# Page_04-LAN9254-Part1.net
KiCad netlist of a schematic drawn in Altium Designer
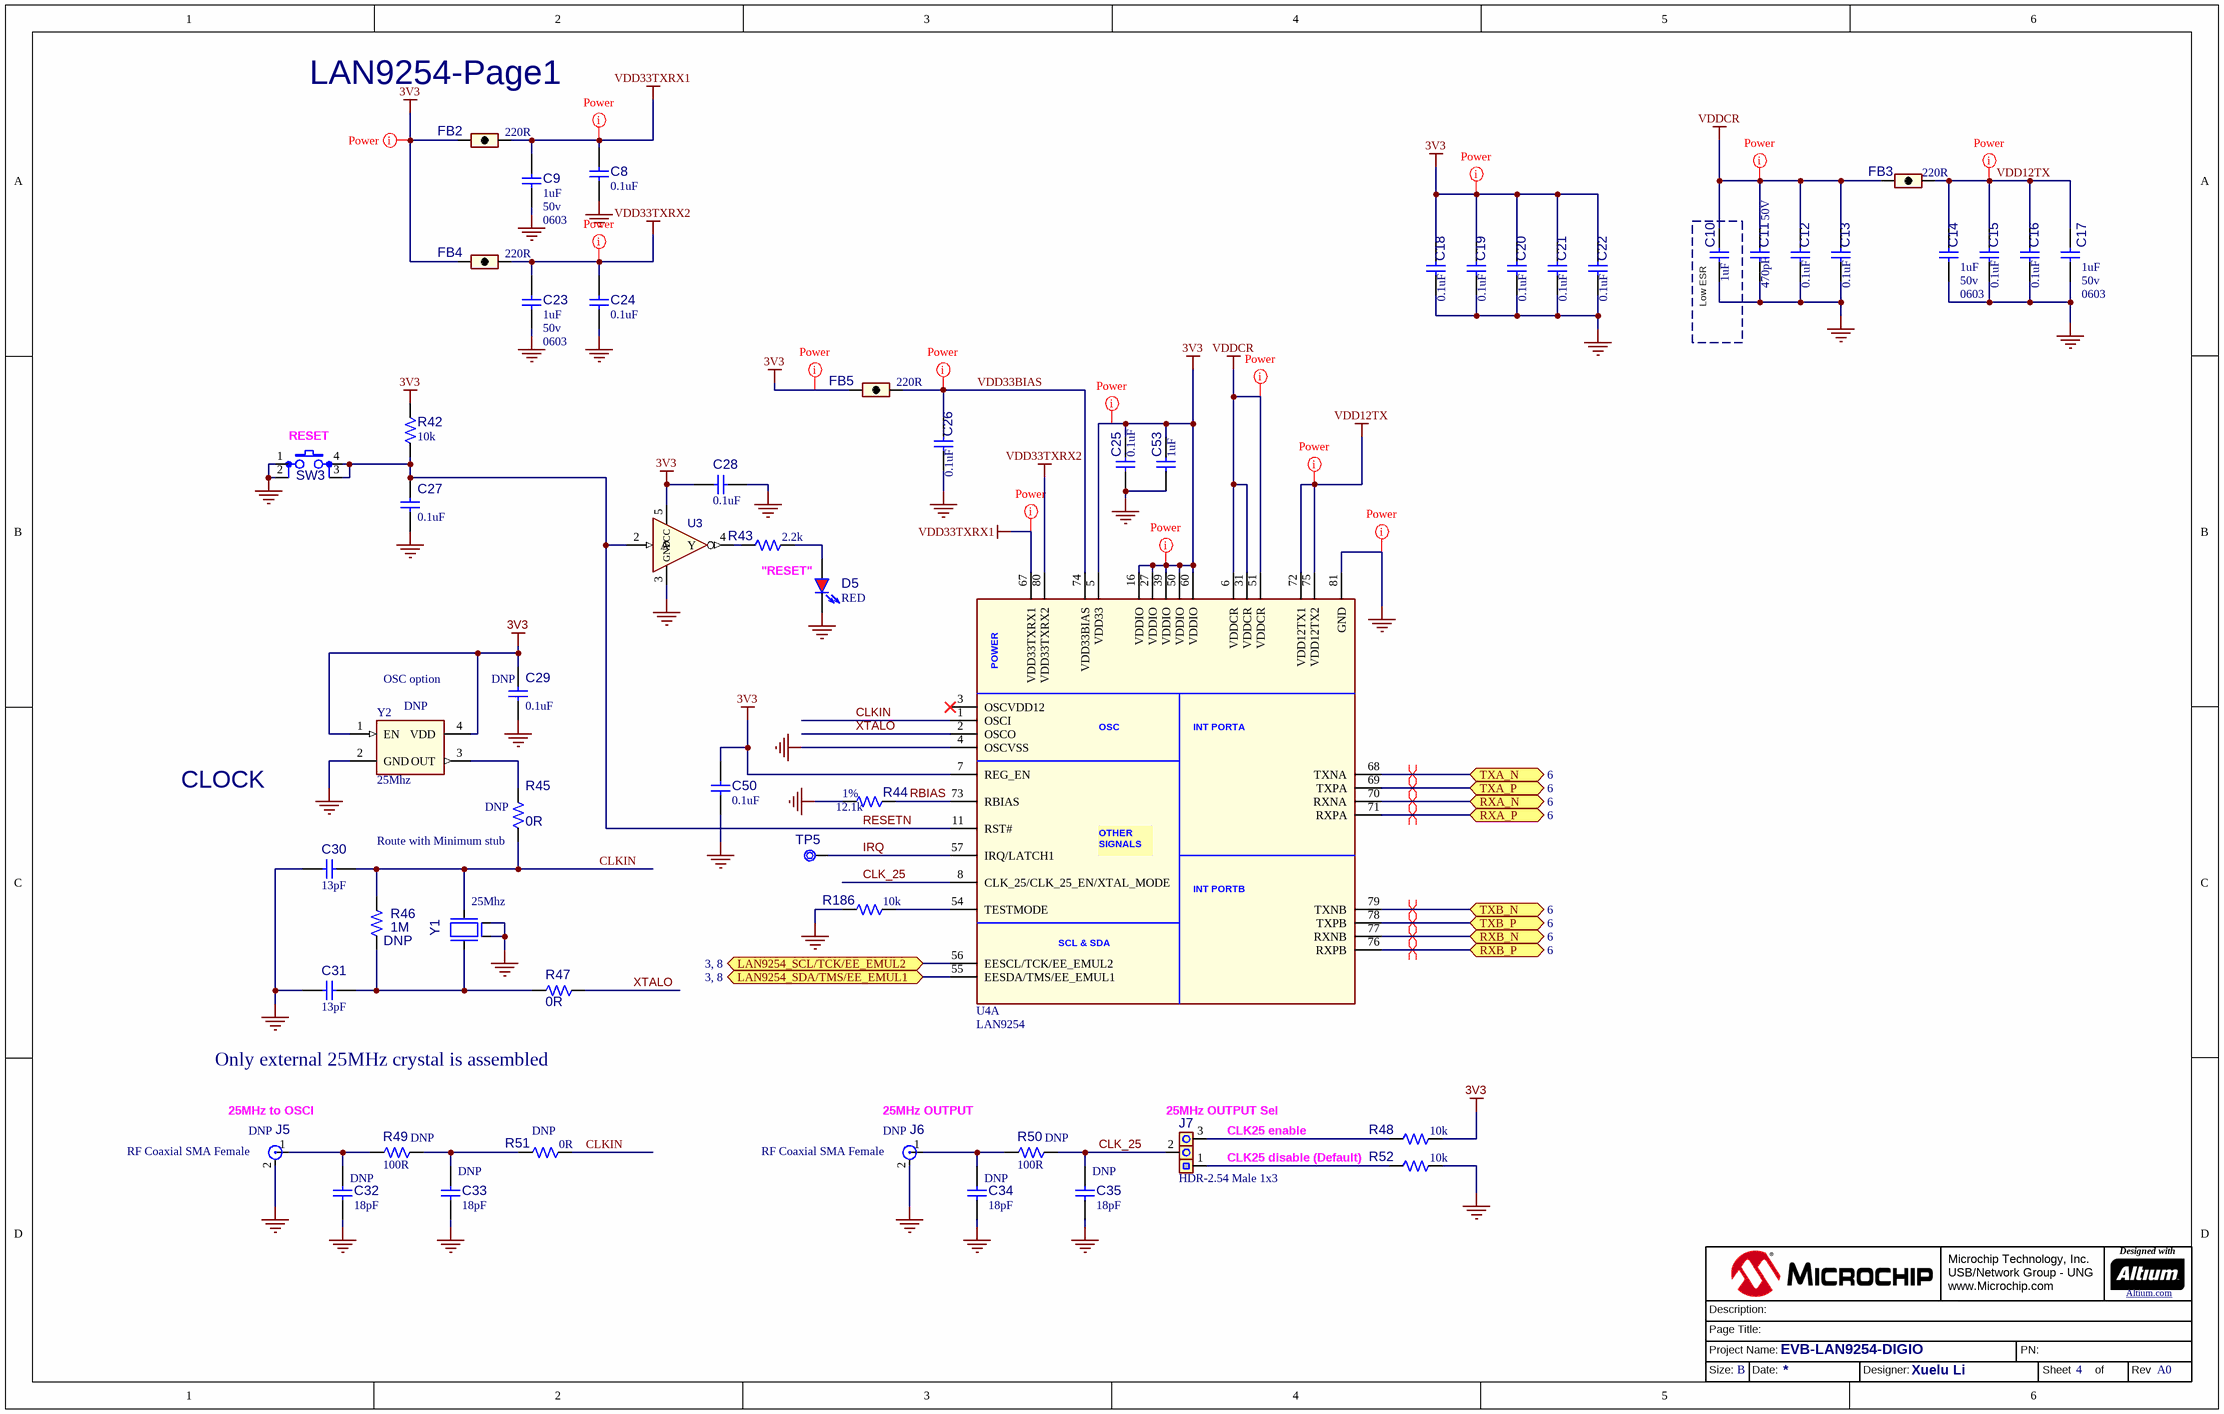
[diagram p0: Page 04-LAN9254-Part1.SchDoc]

(export (version "E")
  (design (tool "Eeschema 10.0.6"))
  (components
    (comp (ref "C8")
      (value "0.1uF")
      (footprint "CAP_C_0402")
      (description "Capacitor")
      (fields
        (field (name "VOLTAGE") "16V")
        (field (name "TOLERANCE") "10%")
        (field (name "OWNER") "Sompoch Loboonlert")
      )
      (libsource (lib "MCHP-CDB-Offline") (part "Capacitor NP"))
    )
    (comp (ref "C9")
      (value "1uF")
      (footprint "CAP_C_0603")
      (description "Capacitor")
      (fields
        (field (name "VOLTAGE") "50v")
        (field (name "PACKAGE") "0603")
        (field (name "TOLERANCE") "10%")
        (field (name "Comment") "Capacitor NP")
        (field (name "OWNER") "Sam Charles")
      )
      (libsource (lib "MCHP-CDB") (part "Capacitor NP"))
    )
    (comp (ref "C10")
      (value "1uF")
      (footprint "CAP_C_0603")
      (description "Capacitor")
      (fields (field (name "VOLTAGE") "50V") (field (name "TOLERANCE") "10%"))
      (libsource (lib "") (part "Capacitor NP_1"))
    )
    (comp (ref "C11")
      (value "470pF")
      (footprint "CAP_C_0402")
      (description "Capacitor")
      (fields
        (field (name "VOLTAGE") "50V")
        (field (name "TOLERANCE") "5%")
        (field (name "Comment") "Capacitor NP")
        (field (name "OWNER") "Duane Burt")
      )
      (libsource (lib "MCHP-CDB") (part "Capacitor NP"))
    )
    (comp (ref "C12")
      (value "0.1uF")
      (footprint "CAP_C_0402")
      (description "Capacitor")
      (fields
        (field (name "TOLERANCE") "10%")
        (field (name "Comment") "Capacitor NP")
        (field (name "OWNER") "Jamus Griego")
      )
      (libsource (lib "MCHP-CDB") (part "Capacitor NP"))
    )
    (comp (ref "C13")
      (value "0.1uF")
      (footprint "CAP_C_0402")
      (description "Capacitor")
      (fields
        (field (name "TOLERANCE") "10%")
        (field (name "Comment") "Capacitor NP")
        (field (name "OWNER") "Jamus Griego")
      )
      (libsource (lib "MCHP-CDB") (part "Capacitor NP"))
    )
    (comp (ref "C14")
      (value "1uF")
      (footprint "CAP_C_0603")
      (description "Capacitor")
      (fields
        (field (name "VOLTAGE") "50v")
        (field (name "PACKAGE") "0603")
        (field (name "TOLERANCE") "10%")
        (field (name "Comment") "Capacitor NP")
        (field (name "OWNER") "Sam Charles")
      )
      (libsource (lib "MCHP-CDB") (part "Capacitor NP"))
    )
    (comp (ref "C15")
      (value "0.1uF")
      (footprint "CAP_C_0402")
      (description "Capacitor")
      (fields
        (field (name "TOLERANCE") "10%")
        (field (name "Comment") "Capacitor NP")
        (field (name "OWNER") "Jamus Griego")
      )
      (libsource (lib "MCHP-CDB") (part "Capacitor NP"))
    )
    (comp (ref "C16")
      (value "0.1uF")
      (footprint "CAP_C_0402")
      (description "Capacitor")
      (fields
        (field (name "TOLERANCE") "10%")
        (field (name "Comment") "Capacitor NP")
        (field (name "OWNER") "Jamus Griego")
      )
      (libsource (lib "MCHP-CDB") (part "Capacitor NP"))
    )
    (comp (ref "C17")
      (value "1uF")
      (footprint "CAP_C_0603")
      (description "Capacitor")
      (fields
        (field (name "VOLTAGE") "50v")
        (field (name "PACKAGE") "0603")
        (field (name "TOLERANCE") "10%")
        (field (name "Comment") "Capacitor NP")
        (field (name "OWNER") "Sam Charles")
      )
      (libsource (lib "MCHP-CDB") (part "Capacitor NP"))
    )
    (comp (ref "C18")
      (value "0.1uF")
      (footprint "CAP_C_0402")
      (description "Capacitor")
      (fields
        (field (name "TOLERANCE") "10%")
        (field (name "Comment") "Capacitor NP")
        (field (name "OWNER") "Jamus Griego")
      )
      (libsource (lib "MCHP-CDB") (part "Capacitor NP"))
    )
    (comp (ref "C19")
      (value "0.1uF")
      (footprint "CAP_C_0402")
      (description "Capacitor")
      (fields
        (field (name "TOLERANCE") "10%")
        (field (name "Comment") "Capacitor NP")
        (field (name "OWNER") "Jamus Griego")
      )
      (libsource (lib "MCHP-CDB") (part "Capacitor NP"))
    )
    (comp (ref "C20")
      (value "0.1uF")
      (footprint "CAP_C_0402")
      (description "Capacitor")
      (fields
        (field (name "TOLERANCE") "10%")
        (field (name "Comment") "Capacitor NP")
        (field (name "OWNER") "Jamus Griego")
      )
      (libsource (lib "MCHP-CDB") (part "Capacitor NP"))
    )
    (comp (ref "C21")
      (value "0.1uF")
      (footprint "CAP_C_0402")
      (description "Capacitor")
      (fields
        (field (name "TOLERANCE") "10%")
        (field (name "Comment") "Capacitor NP")
        (field (name "OWNER") "Jamus Griego")
      )
      (libsource (lib "MCHP-CDB") (part "Capacitor NP"))
    )
    (comp (ref "C22")
      (value "0.1uF")
      (footprint "CAP_C_0402")
      (description "Capacitor")
      (fields
        (field (name "TOLERANCE") "10%")
        (field (name "Comment") "Capacitor NP")
        (field (name "OWNER") "Jamus Griego")
      )
      (libsource (lib "MCHP-CDB") (part "Capacitor NP"))
    )
    (comp (ref "C23")
      (value "1uF")
      (footprint "CAP_C_0603")
      (description "Capacitor")
      (fields
        (field (name "VOLTAGE") "50v")
        (field (name "PACKAGE") "0603")
        (field (name "TOLERANCE") "10%")
        (field (name "Comment") "Capacitor NP")
        (field (name "OWNER") "Sam Charles")
      )
      (libsource (lib "MCHP-CDB") (part "Capacitor NP"))
    )
    (comp (ref "C24")
      (value "0.1uF")
      (footprint "CAP_C_0402")
      (description "Capacitor")
      (fields
        (field (name "VOLTAGE") "16V")
        (field (name "TOLERANCE") "10%")
        (field (name "OWNER") "Sompoch Loboonlert")
      )
      (libsource (lib "MCHP-CDB-Offline") (part "Capacitor NP"))
    )
    (comp (ref "C25")
      (value "0.1uF")
      (footprint "CAP_C_0402")
      (description "Capacitor")
      (fields
        (field (name "TOLERANCE") "10%")
        (field (name "Comment") "Capacitor NP")
        (field (name "OWNER") "Jamus Griego")
      )
      (libsource (lib "MCHP-CDB") (part "Capacitor NP"))
    )
    (comp (ref "C26")
      (value "0.1uF")
      (footprint "CAP_C_0402")
      (description "Capacitor")
      (fields
        (field (name "TOLERANCE") "10%")
        (field (name "Comment") "Capacitor NP")
        (field (name "OWNER") "Jamus Griego")
      )
      (libsource (lib "MCHP-CDB") (part "Capacitor NP"))
    )
    (comp (ref "C27")
      (value "0.1uF")
      (footprint "CAP_C_0402")
      (description "Capacitor")
      (fields
        (field (name "VOLTAGE") "16V")
        (field (name "TOLERANCE") "10%")
        (field (name "OWNER") "Sompoch Loboonlert")
      )
      (libsource (lib "MCHP-CDB-Offline") (part "Capacitor NP"))
    )
    (comp (ref "C28")
      (value "0.1uF")
      (footprint "CAP_C_0402")
      (description "Capacitor")
      (fields
        (field (name "VOLTAGE") "16V")
        (field (name "TOLERANCE") "10%")
        (field (name "OWNER") "Sompoch Loboonlert")
      )
      (libsource (lib "MCHP-CDB-Offline") (part "Capacitor NP"))
    )
    (comp (ref "C29")
      (value "0.1uF")
      (footprint "CAP_C_0402")
      (description "Capacitor")
      (fields
        (field (name "VOLTAGE") "16V")
        (field (name "TOLERANCE") "10%")
        (field (name "POPULATED") "DNP")
        (field (name "OWNER") "Sompoch Loboonlert")
      )
      (libsource (lib "MCHP-CDB-Offline") (part "Capacitor NP"))
    )
    (comp (ref "C30")
      (value "13pF")
      (footprint "CAP_C_0603")
      (description "Capacitor")
      (fields
        (field (name "VOLTAGE") "50V")
        (field (name "TOLERANCE") "5%")
        (field (name "OWNER") "Jamus Griego")
      )
      (libsource (lib "MCHP-CDB") (part "Capacitor NP"))
    )
    (comp (ref "C31")
      (value "13pF")
      (footprint "CAP_C_0603")
      (description "Capacitor")
      (fields
        (field (name "VOLTAGE") "50V")
        (field (name "TOLERANCE") "5%")
        (field (name "OWNER") "Jamus Griego")
      )
      (libsource (lib "MCHP-CDB") (part "Capacitor NP"))
    )
    (comp (ref "C32")
      (value "18pF")
      (footprint "CAP_C_0805")
      (description "Capacitor")
      (fields (field (name "VOLTAGE") "50V") (field (name "TOLERANCE") "5%") (field (name "POPULATED") "DNP"))
      (libsource (lib "MCHP-CDB") (part "Capacitor NP"))
    )
    (comp (ref "C33")
      (value "18pF")
      (footprint "CAP_C_0805")
      (description "Capacitor")
      (fields (field (name "VOLTAGE") "50V") (field (name "TOLERANCE") "5%") (field (name "POPULATED") "DNP"))
      (libsource (lib "MCHP-CDB") (part "Capacitor NP"))
    )
    (comp (ref "C34")
      (value "18pF")
      (footprint "CAP_C_0805")
      (description "Capacitor")
      (fields (field (name "VOLTAGE") "50V") (field (name "TOLERANCE") "5%") (field (name "POPULATED") "DNP"))
      (libsource (lib "MCHP-CDB") (part "Capacitor NP"))
    )
    (comp (ref "C35")
      (value "18pF")
      (footprint "CAP_C_0805")
      (description "Capacitor")
      (fields (field (name "VOLTAGE") "50V") (field (name "TOLERANCE") "5%") (field (name "POPULATED") "DNP"))
      (libsource (lib "MCHP-CDB") (part "Capacitor NP"))
    )
    (comp (ref "C50")
      (value "0.1uF")
      (footprint "CAP_C_0402")
      (description "Capacitor")
      (fields
        (field (name "VOLTAGE") "16V")
        (field (name "TOLERANCE") "10%")
        (field (name "OWNER") "Sompoch Loboonlert")
      )
      (libsource (lib "MCHP-CDB-Offline") (part "Capacitor NP"))
    )
    (comp (ref "C53")
      (value "1uF")
      (footprint "CAP_C_0603")
      (description "Capacitor")
      (fields (field (name "VOLTAGE") "50V") (field (name "TOLERANCE") "10%"))
      (libsource (lib "") (part "Capacitor NP_1"))
    )
    (comp (ref "D5")
      (value "RED")
      (footprint "LED_0603_RED")
      (description "LED")
      (fields (field (name "Comment") "LED_red") (field (name "OWNER") "Sompoch Loboonlert"))
      (libsource (lib "MCHP-CDB") (part "LED_red"))
    )
    (comp (ref "FB2")
      (value "220R")
      (footprint "IND_C_0603")
      (fields (field (name "Comment") "Ferrite Bead") (field (name "OWNER") "Sompoch Loboonlert"))
      (libsource (lib "MCHP-CDB-Offline") (part "Ferrite Bead"))
    )
    (comp (ref "FB3")
      (value "220R")
      (footprint "IND_C_0603")
      (fields (field (name "Comment") "Ferrite Bead") (field (name "OWNER") "Ciprian Abramov"))
      (libsource (lib "MCHP-CDB-Offline") (part "Ferrite Bead"))
    )
    (comp (ref "FB4")
      (value "220R")
      (footprint "IND_C_0603")
      (fields (field (name "Comment") "Ferrite Bead") (field (name "OWNER") "Sompoch Loboonlert"))
      (libsource (lib "MCHP-CDB-Offline") (part "Ferrite Bead"))
    )
    (comp (ref "FB5")
      (value "220R")
      (footprint "IND_C_0603")
      (fields (field (name "Comment") "Ferrite Bead") (field (name "OWNER") "Sompoch Loboonlert"))
      (libsource (lib "MCHP-CDB-Offline") (part "Ferrite Bead"))
    )
    (comp (ref "J5")
      (value "RF Coaxial SMA Female")
      (footprint "CON_JACK_F_TH_V_ACP_901-144-8RFX")
      (description "CON Jack 2 Pins")
      (fields (field (name "POPULATED") "DNP") (field (name "OWNER") "Jairuz Agang-ang"))
      (libsource (lib "MCHP-CDB") (part "CON Jack 2 Pins"))
    )
    (comp (ref "J6")
      (value "RF Coaxial SMA Female")
      (footprint "CON_JACK_F_TH_V_ACP_901-144-8RFX")
      (description "CON Jack 2 Pins")
      (fields (field (name "POPULATED") "DNP") (field (name "OWNER") "Jairuz Agang-ang"))
      (libsource (lib "MCHP-CDB") (part "CON Jack 2 Pins"))
    )
    (comp (ref "J7")
      (value "HDR-2.54 Male 1x3")
      (footprint "HDR_M_2.54_1x3")
      (fields (field (name "Comment") "Header 1x3"))
      (libsource (lib "MCHP-CDB") (part "Header 1x3"))
    )
    (comp (ref "R42")
      (value "10k")
      (footprint "RES_C_0603")
      (description "Resistor")
      (fields (field (name "TOLERANCE") "1%") (field (name "VOLTAGE") "75V"))
      (libsource (lib "MCHP-CDB-Offline") (part "Resistor"))
    )
    (comp (ref "R43")
      (value "2.2k")
      (footprint "RES_C_0603")
      (description "Resistor")
      (fields
        (field (name "TOLERANCE") "1%")
        (field (name "VOLTAGE") "75V")
        (field (name "OWNER") "Bogdan P (M91398)")
      )
      (libsource (lib "") (part "Resistor_1"))
    )
    (comp (ref "R44")
      (value "12.1k")
      (footprint "RES_C_0603")
      (description "Resistor")
      (fields (field (name "TOLERANCE") "1%") (field (name "VOLTAGE") "75V") (field (name "POWER") "1/10W"))
      (libsource (lib "MCHP-CDB") (part "Resistor"))
    )
    (comp (ref "R45")
      (value "0R")
      (footprint "RES_C_0603")
      (description "RES TKF 0R 1/10W SMD 0603")
      (fields
        (field (name "POWER") "1/10W")
        (field (name "POPULATE") "DNP")
        (field (name "Comment") "Resistor")
      )
      (libsource (lib "") (part "Resistor_1"))
    )
    (comp (ref "R46")
      (value "1M")
      (footprint "RES_C_0603")
      (description "RES TKF 1M 1% 1/10W SMD 0603")
      (fields
        (field (name "TOLERANCE") "1%")
        (field (name "VOLTAGE") "75V")
        (field (name "POPULATED") "DNP")
        (field (name "OWNER") "Bogdan P (M91398)")
      )
      (libsource (lib "") (part "Resistor_1"))
    )
    (comp (ref "R47")
      (value "0R")
      (footprint "RES_C_0603")
      (description "RES TKF 0R 1/10W SMD 0603")
      (fields (field (name "POWER") "1/10W") (field (name "Comment") "Resistor"))
      (libsource (lib "") (part "Resistor_1"))
    )
    (comp (ref "R48")
      (value "10k")
      (footprint "RES_C_0603")
      (description "Resistor")
      (fields (field (name "TOLERANCE") "1%") (field (name "POWER") "1/10W"))
      (libsource (lib "MCHP-CDB") (part "Resistor"))
    )
    (comp (ref "R49")
      (value "100R")
      (footprint "RES_C_0805")
      (description "Resistor")
      (fields
        (field (name "TOLERANCE") "5%")
        (field (name "POWER") "1/10W")
        (field (name "POPULATED") "DNP")
        (field (name "OWNER") "Jairuz Agang-ang")
      )
      (libsource (lib "MCHP-CDB") (part "Resistor"))
    )
    (comp (ref "R50")
      (value "100R")
      (footprint "RES_C_0805")
      (description "Resistor")
      (fields
        (field (name "TOLERANCE") "5%")
        (field (name "POWER") "1/10W")
        (field (name "POPULATED") "DNP")
        (field (name "OWNER") "Jairuz Agang-ang")
      )
      (libsource (lib "MCHP-CDB") (part "Resistor"))
    )
    (comp (ref "R51")
      (value "0R")
      (footprint "RES_C_0402")
      (description "Resistor")
      (fields
        (field (name "POWER") "1/16W")
        (field (name "POPULATED") "DNP")
        (field (name "OWNER") "Sompoch Loboonlert")
      )
      (libsource (lib "MCHP-CDB") (part "Resistor"))
    )
    (comp (ref "R52")
      (value "10k")
      (footprint "RES_C_0603")
      (description "Resistor")
      (fields (field (name "TOLERANCE") "1%") (field (name "POWER") "1/10W"))
      (libsource (lib "MCHP-CDB") (part "Resistor"))
    )
    (comp (ref "R186")
      (value "10k")
      (footprint "RES_C_0603")
      (description "Resistor")
      (fields (field (name "TOLERANCE") "1%") (field (name "POWER") "1/10W"))
      (libsource (lib "MCHP-CDB") (part "Resistor"))
    )
    (comp (ref "SW3")
      (value "Switch 4 Pin")
      (footprint "SW_TACT_SMD_CK_PTS810SJM")
      (description "Switch")
      (fields (field (name "VOLTAGE") "16V") (field (name "OWNER") "Sam Charles"))
      (libsource (lib "MCHP-CDB") (part "Switch 4 Pin"))
    )
    (comp (ref "TP5")
      (value "Test Point No BOM")
      (footprint "TP_1.2x0.7")
      (description "Test Point")
      (fields (field (name "OWNER") "Bogdan P (M91398)"))
      (libsource (lib "MCHP-CDB") (part "Test Point No BOM"))
    )
    (comp (ref "U3")
      (value "74AHC1G14 SC-70-5")
      (footprint "SC-70-5")
      (fields (field (name "OWNER") "Cristian Papuc"))
      (libsource (lib "MCHP-CDB") (part "74AHC1G14 SC-70-5"))
    )
    (comp (ref "U4")
      (value "LAN9254")
      (footprint "TQFP-80_12x12_EP6x6")
      (fields (field (name "Comment") "LAN9254-SVB TQFP80") (field (name "OWNER") "Manikandan Balakrishnan"))
      (libsource (lib "MCHP-CDB") (part "LAN9254-SVB TQFP80"))
    )
    (comp (ref "Y1")
      (value "25Mhz")
      (footprint "CRYSTAL_XRCGB_L2W1.6H0.7")
      (fields
        (field (name "TOLERANCE") "±35ppm")
        (field (name "Comment") "Crystal 4 Pins")
        (field (name "OWNER") "Sam Charles")
      )
      (libsource (lib "MCHP-CDB") (part "Crystal 4 Pins"))
    )
    (comp (ref "Y2")
      (value "25Mhz")
      (footprint "OSCILLATOR_KC2520B-C1")
      (fields
        (field (name "VOLTAGE") "1.8-3.3V")
        (field (name "TOLERANCE") "±50ppm")
        (field (name "POPULATED") "DNP")
        (field (name "Comment") "OSCILLATOR 4 Pins")
        (field (name "OWNER") "Jamus Griego")
      )
      (libsource (lib "MCHP-CDB") (part "OSCILLATOR 4 Pins"))
    )
  )
  (nets
    (net (code "1") (name "/CLKIN") (class "Default")
      (node (ref "C30") (pin "2") (pinfunction "2_2") (pintype "passive"))
      (node (ref "R45") (pin "1") (pinfunction "1_1") (pintype "passive"))
      (node (ref "R46") (pin "2") (pinfunction "2_2") (pintype "passive"))
      (node (ref "R51") (pin "2") (pinfunction "2_2") (pintype "passive"))
      (node (ref "U4") (pin "1") (pinfunction "OSCI_1") (pintype "passive"))
      (node (ref "Y1") (pin "3") (pinfunction "Osc2_3") (pintype "passive"))
    )
    (net (code "2") (name "/CLK_25") (class "Default")
      (node (ref "C35") (pin "2") (pinfunction "2_2") (pintype "passive"))
      (node (ref "J7") (pin "2") (pinfunction "2_2") (pintype "passive"))
      (node (ref "R50") (pin "2") (pinfunction "2_2") (pintype "passive"))
      (node (ref "U4") (pin "8") (pinfunction "CLK_25/CLK_25_EN/XTAL_MODE_8") (pintype "passive"))
    )
    (net (code "3") (name "/IRQ") (class "Default")
      (node (ref "TP5") (pin "1") (pinfunction "1_1") (pintype "passive"))
      (node (ref "U4") (pin "57") (pinfunction "IRQ/LATCH1_57") (pintype "passive"))
    )
    (net (code "4") (name "/LAN9254_SCL{slash}TCK{slash}EE_EMUL2") (class "Default")
      (node (ref "U4") (pin "56") (pinfunction "EESCL/TCK/EE_EMUL2_56") (pintype "passive"))
    )
    (net (code "5") (name "/LAN9254_SDA{slash}TMS{slash}EE_EMUL1") (class "Default")
      (node (ref "U4") (pin "55") (pinfunction "EESDA/TMS/EE_EMUL1_55") (pintype "passive"))
    )
    (net (code "6") (name "/RBIAS") (class "Default")
      (node (ref "R44") (pin "2") (pinfunction "2_2") (pintype "passive"))
      (node (ref "U4") (pin "73") (pinfunction "RBIAS_73") (pintype "passive"))
    )
    (net (code "7") (name "/RESETN") (class "Default")
      (node (ref "C27") (pin "2") (pinfunction "2_2") (pintype "passive"))
      (node (ref "R42") (pin "2") (pinfunction "2_2") (pintype "passive"))
      (node (ref "SW3") (pin "3") (pinfunction "3_3") (pintype "passive"))
      (node (ref "SW3") (pin "4") (pinfunction "4_4") (pintype "passive"))
      (node (ref "U3") (pin "2") (pinfunction "A_2") (pintype "input"))
      (node (ref "U4") (pin "11") (pinfunction "RST#_11") (pintype "passive"))
    )
    (net (code "8") (name "/RXA_N") (class "Default")
      (node (ref "U4") (pin "70") (pinfunction "RXNA_70") (pintype "passive"))
    )
    (net (code "9") (name "/RXA_P") (class "Default")
      (node (ref "U4") (pin "71") (pinfunction "RXPA_71") (pintype "passive"))
    )
    (net (code "10") (name "/RXB_N") (class "Default")
      (node (ref "U4") (pin "77") (pinfunction "RXNB_77") (pintype "passive"))
    )
    (net (code "11") (name "/RXB_P") (class "Default")
      (node (ref "U4") (pin "76") (pinfunction "RXPB_76") (pintype "passive"))
    )
    (net (code "12") (name "/TXA_N") (class "Default")
      (node (ref "U4") (pin "68") (pinfunction "TXNA_68") (pintype "passive"))
    )
    (net (code "13") (name "/TXA_P") (class "Default")
      (node (ref "U4") (pin "69") (pinfunction "TXPA_69") (pintype "passive"))
    )
    (net (code "14") (name "/TXB_N") (class "Default")
      (node (ref "U4") (pin "79") (pinfunction "TXNB_79") (pintype "passive"))
    )
    (net (code "15") (name "/TXB_P") (class "Default")
      (node (ref "U4") (pin "78") (pinfunction "TXPB_78") (pintype "passive"))
    )
    (net (code "16") (name "/VDD33BIAS") (class "Default")
      (node (ref "C26") (pin "2") (pinfunction "2_2") (pintype "passive"))
      (node (ref "FB5") (pin "2") (pinfunction "2_2") (pintype "passive"))
      (node (ref "U4") (pin "74") (pinfunction "VDD33BIAS_74") (pintype "passive"))
    )
    (net (code "17") (name "/XTALO") (class "Default")
      (node (ref "R47") (pin "1") (pinfunction "1_1") (pintype "passive"))
      (node (ref "U4") (pin "2") (pinfunction "OSCO_2") (pintype "passive"))
    )
    (net (code "18") (name "3V3") (class "Default")
      (node (ref "C18") (pin "2") (pinfunction "2_2") (pintype "passive"))
      (node (ref "C19") (pin "2") (pinfunction "2_2") (pintype "passive"))
      (node (ref "C20") (pin "2") (pinfunction "2_2") (pintype "passive"))
      (node (ref "C21") (pin "2") (pinfunction "2_2") (pintype "passive"))
      (node (ref "C22") (pin "2") (pinfunction "2_2") (pintype "passive"))
      (node (ref "C25") (pin "2") (pinfunction "2_2") (pintype "passive"))
      (node (ref "C28") (pin "2") (pinfunction "2_2") (pintype "passive"))
      (node (ref "C29") (pin "2") (pinfunction "2_2") (pintype "passive"))
      (node (ref "C50") (pin "1") (pinfunction "1_1") (pintype "passive"))
      (node (ref "C53") (pin "2") (pinfunction "2_2") (pintype "passive"))
      (node (ref "FB2") (pin "1") (pinfunction "1_1") (pintype "passive"))
      (node (ref "FB4") (pin "1") (pinfunction "1_1") (pintype "passive"))
      (node (ref "FB5") (pin "1") (pinfunction "1_1") (pintype "passive"))
      (node (ref "R42") (pin "1") (pinfunction "1_1") (pintype "passive"))
      (node (ref "R48") (pin "1") (pinfunction "1_1") (pintype "passive"))
      (node (ref "U3") (pin "5") (pinfunction "VCC_5") (pintype "power_in"))
      (node (ref "U4") (pin "16") (pinfunction "VDDIO_16") (pintype "passive"))
      (node (ref "U4") (pin "27") (pinfunction "VDDIO_27") (pintype "passive"))
      (node (ref "U4") (pin "39") (pinfunction "VDDIO_39") (pintype "passive"))
      (node (ref "U4") (pin "5") (pinfunction "VDD33_5") (pintype "passive"))
      (node (ref "U4") (pin "50") (pinfunction "VDDIO_50") (pintype "passive"))
      (node (ref "U4") (pin "60") (pinfunction "VDDIO_60") (pintype "passive"))
      (node (ref "U4") (pin "7") (pinfunction "REG_EN_7") (pintype "passive"))
      (node (ref "Y2") (pin "1") (pinfunction "EN_1") (pintype "input"))
      (node (ref "Y2") (pin "4") (pinfunction "VDD_4") (pintype "power_in"))
    )
    (net (code "19") (name "GND") (class "Default")
      (node (ref "C10") (pin "1") (pinfunction "1_1") (pintype "passive"))
      (node (ref "C11") (pin "1") (pinfunction "1_1") (pintype "passive"))
      (node (ref "C12") (pin "1") (pinfunction "1_1") (pintype "passive"))
      (node (ref "C13") (pin "1") (pinfunction "1_1") (pintype "passive"))
      (node (ref "C14") (pin "1") (pinfunction "1_1") (pintype "passive"))
      (node (ref "C15") (pin "1") (pinfunction "1_1") (pintype "passive"))
      (node (ref "C16") (pin "1") (pinfunction "1_1") (pintype "passive"))
      (node (ref "C17") (pin "1") (pinfunction "1_1") (pintype "passive"))
      (node (ref "C18") (pin "1") (pinfunction "1_1") (pintype "passive"))
      (node (ref "C19") (pin "1") (pinfunction "1_1") (pintype "passive"))
      (node (ref "C20") (pin "1") (pinfunction "1_1") (pintype "passive"))
      (node (ref "C21") (pin "1") (pinfunction "1_1") (pintype "passive"))
      (node (ref "C22") (pin "1") (pinfunction "1_1") (pintype "passive"))
      (node (ref "C23") (pin "1") (pinfunction "1_1") (pintype "passive"))
      (node (ref "C24") (pin "2") (pinfunction "2_2") (pintype "passive"))
      (node (ref "C25") (pin "1") (pinfunction "1_1") (pintype "passive"))
      (node (ref "C26") (pin "1") (pinfunction "1_1") (pintype "passive"))
      (node (ref "C27") (pin "1") (pinfunction "1_1") (pintype "passive"))
      (node (ref "C28") (pin "1") (pinfunction "1_1") (pintype "passive"))
      (node (ref "C29") (pin "1") (pinfunction "1_1") (pintype "passive"))
      (node (ref "C30") (pin "1") (pinfunction "1_1") (pintype "passive"))
      (node (ref "C31") (pin "1") (pinfunction "1_1") (pintype "passive"))
      (node (ref "C32") (pin "1") (pinfunction "1_1") (pintype "passive"))
      (node (ref "C33") (pin "1") (pinfunction "1_1") (pintype "passive"))
      (node (ref "C34") (pin "1") (pinfunction "1_1") (pintype "passive"))
      (node (ref "C35") (pin "1") (pinfunction "1_1") (pintype "passive"))
      (node (ref "C50") (pin "2") (pinfunction "2_2") (pintype "passive"))
      (node (ref "C53") (pin "1") (pinfunction "1_1") (pintype "passive"))
      (node (ref "C8") (pin "2") (pinfunction "2_2") (pintype "passive"))
      (node (ref "C9") (pin "1") (pinfunction "1_1") (pintype "passive"))
      (node (ref "D5") (pin "2") (pinfunction "K_2") (pintype "passive"))
      (node (ref "J5") (pin "2") (pinfunction "2_2") (pintype "passive"))
      (node (ref "J6") (pin "2") (pinfunction "2_2") (pintype "passive"))
      (node (ref "R186") (pin "2") (pinfunction "2_2") (pintype "passive"))
      (node (ref "R44") (pin "1") (pinfunction "1_1") (pintype "passive"))
      (node (ref "R52") (pin "1") (pinfunction "1_1") (pintype "passive"))
      (node (ref "SW3") (pin "1") (pinfunction "1_1") (pintype "passive"))
      (node (ref "SW3") (pin "2") (pinfunction "2_2") (pintype "passive"))
      (node (ref "U3") (pin "3") (pinfunction "GND_3") (pintype "power_in"))
      (node (ref "U4") (pin "4") (pinfunction "OSCVSS_4") (pintype "passive"))
      (node (ref "U4") (pin "81") (pinfunction "GND_81") (pintype "passive"))
      (node (ref "Y1") (pin "2") (pinfunction "GND_2") (pintype "power_in"))
      (node (ref "Y1") (pin "4") (pinfunction "GND_4") (pintype "power_in"))
      (node (ref "Y2") (pin "2") (pinfunction "GND_2") (pintype "power_in"))
    )
    (net (code "20") (name "Net-(C32-Pad2)") (class "Default")
      (node (ref "C32") (pin "2") (pinfunction "2_2") (pintype "passive"))
      (node (ref "J5") (pin "1") (pinfunction "1_1") (pintype "passive"))
      (node (ref "R49") (pin "1") (pinfunction "1_1") (pintype "passive"))
    )
    (net (code "21") (name "Net-(C33-Pad2)") (class "Default")
      (node (ref "C33") (pin "2") (pinfunction "2_2") (pintype "passive"))
      (node (ref "R49") (pin "2") (pinfunction "2_2") (pintype "passive"))
      (node (ref "R51") (pin "1") (pinfunction "1_1") (pintype "passive"))
    )
    (net (code "22") (name "Net-(C34-Pad2)") (class "Default")
      (node (ref "C34") (pin "2") (pinfunction "2_2") (pintype "passive"))
      (node (ref "J6") (pin "1") (pinfunction "1_1") (pintype "passive"))
      (node (ref "R50") (pin "1") (pinfunction "1_1") (pintype "passive"))
    )
    (net (code "23") (name "Net-(D5-A)") (class "Default")
      (node (ref "D5") (pin "1") (pinfunction "A_1") (pintype "passive"))
      (node (ref "R43") (pin "1") (pinfunction "1_1") (pintype "passive"))
    )
    (net (code "24") (name "Net-(J7-Pad1)") (class "Default")
      (node (ref "J7") (pin "1") (pinfunction "1_1") (pintype "passive"))
      (node (ref "R52") (pin "2") (pinfunction "2_2") (pintype "passive"))
    )
    (net (code "25") (name "Net-(J7-Pad3)") (class "Default")
      (node (ref "J7") (pin "3") (pinfunction "3_3") (pintype "passive"))
      (node (ref "R48") (pin "2") (pinfunction "2_2") (pintype "passive"))
    )
    (net (code "26") (name "Net-(U3-Y)") (class "Default")
      (node (ref "R43") (pin "2") (pinfunction "2_2") (pintype "passive"))
      (node (ref "U3") (pin "4") (pinfunction "Y_4") (pintype "output"))
    )
    (net (code "27") (name "Net-(U4A-TESTMODE)") (class "Default")
      (node (ref "R186") (pin "1") (pinfunction "1_1") (pintype "passive"))
      (node (ref "U4") (pin "54") (pinfunction "TESTMODE_54") (pintype "passive"))
    )
    (net (code "28") (name "Net-(Y1-Osc1)") (class "Default")
      (node (ref "C31") (pin "2") (pinfunction "2_2") (pintype "passive"))
      (node (ref "R46") (pin "1") (pinfunction "1_1") (pintype "passive"))
      (node (ref "R47") (pin "2") (pinfunction "2_2") (pintype "passive"))
      (node (ref "Y1") (pin "1") (pinfunction "Osc1_1") (pintype "passive"))
    )
    (net (code "29") (name "Net-(Y2-OUT)") (class "Default")
      (node (ref "R45") (pin "2") (pinfunction "2_2") (pintype "passive"))
      (node (ref "Y2") (pin "3") (pinfunction "OUT_3") (pintype "output"))
    )
    (net (code "30") (name "VDD12TX") (class "Default")
      (node (ref "C14") (pin "2") (pinfunction "2_2") (pintype "passive"))
      (node (ref "C15") (pin "2") (pinfunction "2_2") (pintype "passive"))
      (node (ref "C16") (pin "2") (pinfunction "2_2") (pintype "passive"))
      (node (ref "C17") (pin "2") (pinfunction "2_2") (pintype "passive"))
      (node (ref "FB3") (pin "2") (pinfunction "2_2") (pintype "passive"))
      (node (ref "U4") (pin "72") (pinfunction "VDD12TX1_72") (pintype "passive"))
      (node (ref "U4") (pin "75") (pinfunction "VDD12TX2_75") (pintype "passive"))
    )
    (net (code "31") (name "VDD33TXRX1") (class "Default")
      (node (ref "C8") (pin "1") (pinfunction "1_1") (pintype "passive"))
      (node (ref "C9") (pin "2") (pinfunction "2_2") (pintype "passive"))
      (node (ref "FB2") (pin "2") (pinfunction "2_2") (pintype "passive"))
      (node (ref "U4") (pin "67") (pinfunction "VDD33TXRX1_67") (pintype "passive"))
    )
    (net (code "32") (name "VDD33TXRX2") (class "Default")
      (node (ref "C23") (pin "2") (pinfunction "2_2") (pintype "passive"))
      (node (ref "C24") (pin "1") (pinfunction "1_1") (pintype "passive"))
      (node (ref "FB4") (pin "2") (pinfunction "2_2") (pintype "passive"))
      (node (ref "U4") (pin "80") (pinfunction "VDD33TXRX2_80") (pintype "passive"))
    )
    (net (code "33") (name "VDDCR") (class "Default")
      (node (ref "C10") (pin "2") (pinfunction "2_2") (pintype "passive"))
      (node (ref "C11") (pin "2") (pinfunction "2_2") (pintype "passive"))
      (node (ref "C12") (pin "2") (pinfunction "2_2") (pintype "passive"))
      (node (ref "C13") (pin "2") (pinfunction "2_2") (pintype "passive"))
      (node (ref "FB3") (pin "1") (pinfunction "1_1") (pintype "passive"))
      (node (ref "U4") (pin "31") (pinfunction "VDDCR_31") (pintype "passive"))
      (node (ref "U4") (pin "51") (pinfunction "VDDCR_51") (pintype "passive"))
      (node (ref "U4") (pin "6") (pinfunction "VDDCR_6") (pintype "passive"))
    )
    (net (code "34") (name "unconnected-(U3-NC-Pad1)") (class "Default")
      (node (ref "U3") (pin "1") (pinfunction "NC_1") (pintype "passive"))
    )
    (net (code "35") (name "unconnected-(U4A-OSCVDD12-Pad3)") (class "Default")
      (node (ref "U4") (pin "3") (pinfunction "OSCVDD12_3") (pintype "passive+no_connect"))
    )
  )
)
